# Connectors.net
KiCad netlist of a schematic drawn in Altium Designer
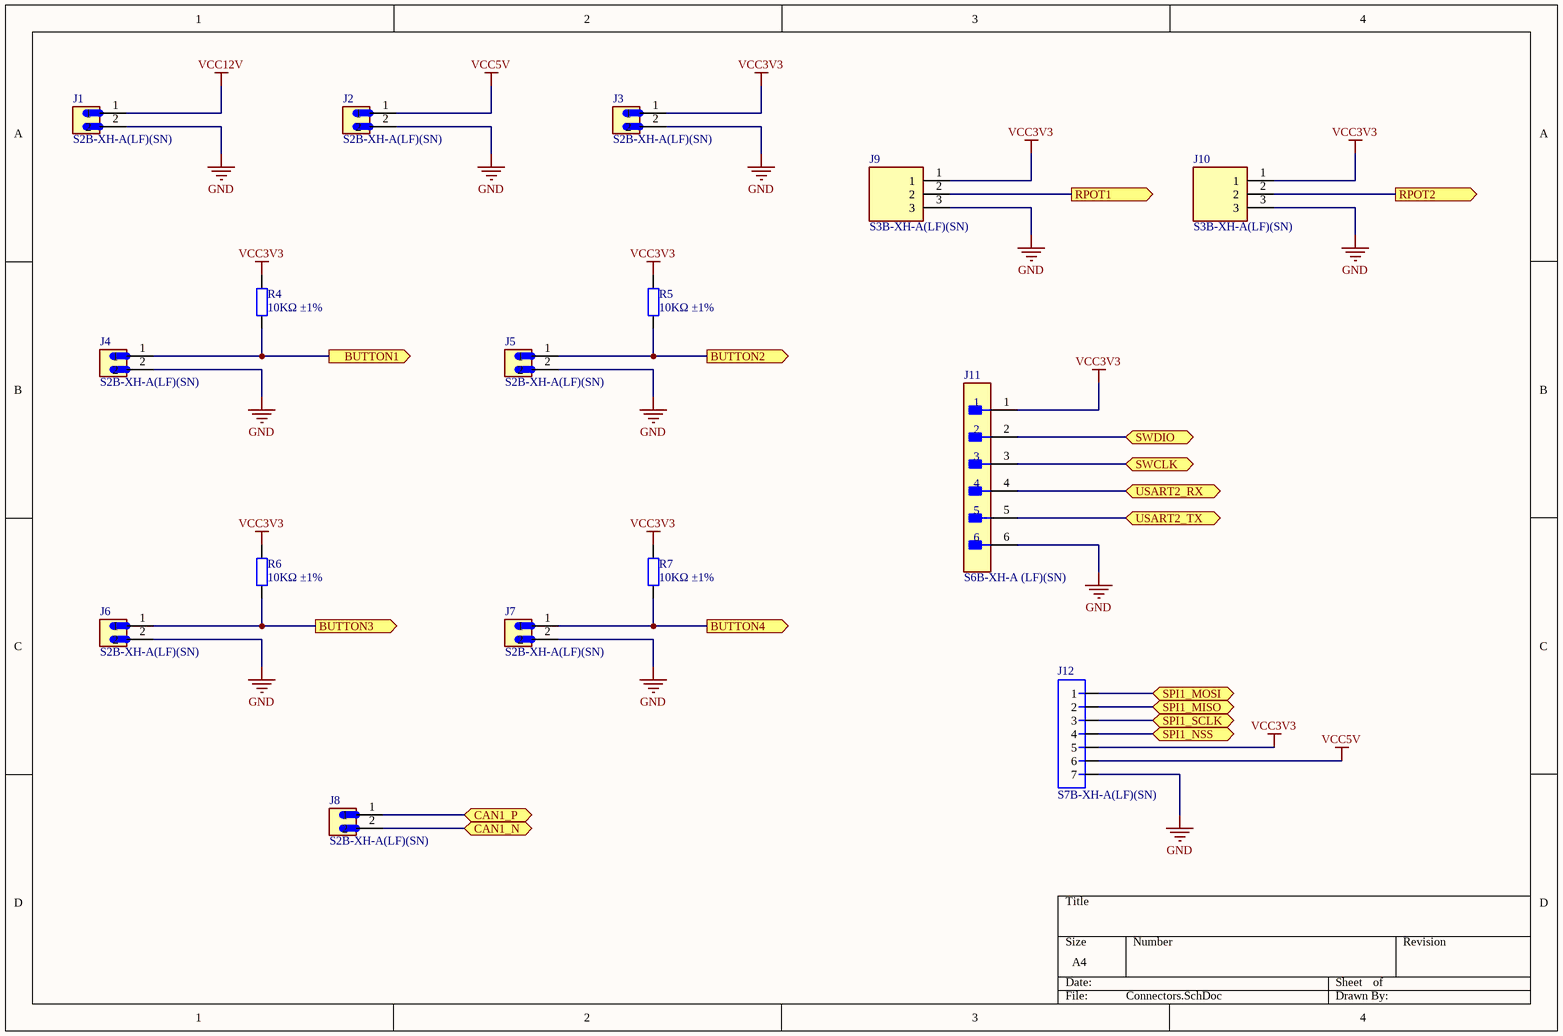
[diagram p0: Connectors.SchDoc]

(export (version "E")
  (design (tool "Eeschema 10.0.6"))
  (components
    (comp (ref "J1")
      (value "S2B-XH-A(LF)(SN)")
      (footprint "JST_S2B-XH-A(LF)(SN)")
      (description "Connector Header Through Hole, Right Angle 2 position 0.098 (2.50mm)")
      (fields (field (name "MF") "JST Sales") (field (name "DIGI-KEY_PART_NUMBER") "455-2257-ND"))
      (libsource (lib "S2B-XH-A_LF__SN_") (part "S2B-XH-A(LF)(SN)"))
    )
    (comp (ref "J2")
      (value "S2B-XH-A(LF)(SN)")
      (footprint "JST_S2B-XH-A(LF)(SN)")
      (description "Connector Header Through Hole, Right Angle 2 position 0.098 (2.50mm)")
      (fields (field (name "MF") "JST Sales") (field (name "DIGI-KEY_PART_NUMBER") "455-2257-ND"))
      (libsource (lib "S2B-XH-A_LF__SN_") (part "S2B-XH-A(LF)(SN)"))
    )
    (comp (ref "J3")
      (value "S2B-XH-A(LF)(SN)")
      (footprint "JST_S2B-XH-A(LF)(SN)")
      (description "Connector Header Through Hole, Right Angle 2 position 0.098 (2.50mm)")
      (fields (field (name "MF") "JST Sales") (field (name "DIGI-KEY_PART_NUMBER") "455-2257-ND"))
      (libsource (lib "S2B-XH-A_LF__SN_") (part "S2B-XH-A(LF)(SN)"))
    )
    (comp (ref "J4")
      (value "S2B-XH-A(LF)(SN)")
      (footprint "JST_S2B-XH-A(LF)(SN)")
      (description "Connector Header Through Hole, Right Angle 2 position 0.098 (2.50mm)")
      (fields (field (name "MF") "JST Sales") (field (name "DIGI-KEY_PART_NUMBER") "455-2257-ND"))
      (libsource (lib "S2B-XH-A_LF__SN_") (part "S2B-XH-A(LF)(SN)"))
    )
    (comp (ref "J5")
      (value "S2B-XH-A(LF)(SN)")
      (footprint "JST_S2B-XH-A(LF)(SN)")
      (description "Connector Header Through Hole, Right Angle 2 position 0.098 (2.50mm)")
      (fields (field (name "MF") "JST Sales") (field (name "DIGI-KEY_PART_NUMBER") "455-2257-ND"))
      (libsource (lib "S2B-XH-A_LF__SN_") (part "S2B-XH-A(LF)(SN)"))
    )
    (comp (ref "J6")
      (value "S2B-XH-A(LF)(SN)")
      (footprint "JST_S2B-XH-A(LF)(SN)")
      (description "Connector Header Through Hole, Right Angle 2 position 0.098 (2.50mm)")
      (fields (field (name "MF") "JST Sales") (field (name "DIGI-KEY_PART_NUMBER") "455-2257-ND"))
      (libsource (lib "S2B-XH-A_LF__SN_") (part "S2B-XH-A(LF)(SN)"))
    )
    (comp (ref "J7")
      (value "S2B-XH-A(LF)(SN)")
      (footprint "JST_S2B-XH-A(LF)(SN)")
      (description "Connector Header Through Hole, Right Angle 2 position 0.098 (2.50mm)")
      (fields (field (name "MF") "JST Sales") (field (name "DIGI-KEY_PART_NUMBER") "455-2257-ND"))
      (libsource (lib "S2B-XH-A_LF__SN_") (part "S2B-XH-A(LF)(SN)"))
    )
    (comp (ref "J8")
      (value "S2B-XH-A(LF)(SN)")
      (footprint "JST_S2B-XH-A(LF)(SN)")
      (description "Connector Header Through Hole, Right Angle 2 position 0.098 (2.50mm)")
      (fields (field (name "MF") "JST Sales") (field (name "DIGI-KEY_PART_NUMBER") "455-2257-ND"))
      (libsource (lib "S2B-XH-A_LF__SN_") (part "S2B-XH-A(LF)(SN)"))
    )
    (comp (ref "J9")
      (value "S3B-XH-A(LF)(SN)")
      (footprint "JST_S3B-XH-A(LF)(SN)")
      (fields (field (name "MF") "JST") (field (name "MP") "S3B-XH-A (LF)(SN)"))
      (libsource (lib "S3B-XH-A_LF__SN_") (part "S3B-XH-A(LF)(SN)"))
    )
    (comp (ref "J10")
      (value "S3B-XH-A(LF)(SN)")
      (footprint "JST_S3B-XH-A(LF)(SN)")
      (fields (field (name "MF") "JST") (field (name "MP") "S3B-XH-A (LF)(SN)"))
      (libsource (lib "S3B-XH-A_LF__SN_") (part "S3B-XH-A(LF)(SN)"))
    )
    (comp (ref "J11")
      (value "S6B-XH-A (LF)(SN)")
      (footprint "FP-S6B-XH-A_LF_SN-MFG")
      (description "CONN HEADER R/A 6POS 2.5MM")
      (libsource (lib "Altium Content Vault") (part "f2cb566baf1c37ab5a3b8e90bbeafd6"))
    )
    (comp (ref "J12")
      (value "S7B-XH-A(LF)(SN)")
      (footprint "JST_S7B-XH-A(LF)(SN)")
      (description "Connector Header Through Hole, Right Angle 7 position 0.098 _2.50mm_")
      (fields (field (name "MP") "S7B-XH-A_LF__SN_") (field (name "MF") "JST Sales"))
      (libsource (lib "S7B-XH-A_LF__SN_") (part "S7B-XH-A(LF)(SN)"))
    )
    (comp (ref "R4")
      (value "10KΩ ±1%")
      (footprint "0402_R")
      (description "Chip resistor")
      (fields (field (name "MANUFACTURER") "Uniroyal Elec") (field (name "PARTNUMBER") "0402WGF1002TCE"))
      (libsource (lib "RES") (part "0402 10K (1002) 1%"))
    )
    (comp (ref "R5")
      (value "10KΩ ±1%")
      (footprint "0402_R")
      (description "Chip resistor")
      (fields (field (name "MANUFACTURER") "Uniroyal Elec") (field (name "PARTNUMBER") "0402WGF1002TCE"))
      (libsource (lib "RES") (part "0402 10K (1002) 1%"))
    )
    (comp (ref "R6")
      (value "10KΩ ±1%")
      (footprint "0402_R")
      (description "Chip resistor")
      (fields (field (name "MANUFACTURER") "Uniroyal Elec") (field (name "PARTNUMBER") "0402WGF1002TCE"))
      (libsource (lib "RES") (part "0402 10K (1002) 1%"))
    )
    (comp (ref "R7")
      (value "10KΩ ±1%")
      (footprint "0402_R")
      (description "Chip resistor")
      (fields (field (name "MANUFACTURER") "Uniroyal Elec") (field (name "PARTNUMBER") "0402WGF1002TCE"))
      (libsource (lib "RES") (part "0402 10K (1002) 1%"))
    )
  )
  (nets
    (net (code "1") (name "/BUTTON1") (class "Default")
      (node (ref "J4") (pin "1") (pinfunction "1_1") (pintype "passive"))
      (node (ref "R4") (pin "1") (pinfunction "1_1") (pintype "passive"))
    )
    (net (code "2") (name "/BUTTON2") (class "Default")
      (node (ref "J5") (pin "1") (pinfunction "1_1") (pintype "passive"))
      (node (ref "R5") (pin "1") (pinfunction "1_1") (pintype "passive"))
    )
    (net (code "3") (name "/BUTTON3") (class "Default")
      (node (ref "J6") (pin "1") (pinfunction "1_1") (pintype "passive"))
      (node (ref "R6") (pin "1") (pinfunction "1_1") (pintype "passive"))
    )
    (net (code "4") (name "/BUTTON4") (class "Default")
      (node (ref "J7") (pin "1") (pinfunction "1_1") (pintype "passive"))
      (node (ref "R7") (pin "1") (pinfunction "1_1") (pintype "passive"))
    )
    (net (code "5") (name "/CAN1_N") (class "Default")
      (node (ref "J8") (pin "2") (pinfunction "2_2") (pintype "passive"))
    )
    (net (code "6") (name "/CAN1_P") (class "Default")
      (node (ref "J8") (pin "1") (pinfunction "1_1") (pintype "passive"))
    )
    (net (code "7") (name "/RPOT1") (class "Default")
      (node (ref "J9") (pin "2") (pinfunction "2_2") (pintype "passive"))
    )
    (net (code "8") (name "/RPOT2") (class "Default")
      (node (ref "J10") (pin "2") (pinfunction "2_2") (pintype "passive"))
    )
    (net (code "9") (name "/SPI1_MISO") (class "Default")
      (node (ref "J12") (pin "2") (pinfunction "2_2") (pintype "passive"))
    )
    (net (code "10") (name "/SPI1_MOSI") (class "Default")
      (node (ref "J12") (pin "1") (pinfunction "1_1") (pintype "passive"))
    )
    (net (code "11") (name "/SPI1_NSS") (class "Default")
      (node (ref "J12") (pin "4") (pinfunction "4_4") (pintype "passive"))
    )
    (net (code "12") (name "/SPI1_SCLK") (class "Default")
      (node (ref "J12") (pin "3") (pinfunction "3_3") (pintype "passive"))
    )
    (net (code "13") (name "/SWCLK") (class "Default")
      (node (ref "J11") (pin "3") (pinfunction "3_3") (pintype "passive"))
    )
    (net (code "14") (name "/SWDIO") (class "Default")
      (node (ref "J11") (pin "2") (pinfunction "2_2") (pintype "passive"))
    )
    (net (code "15") (name "/USART2_RX") (class "Default")
      (node (ref "J11") (pin "4") (pinfunction "4_4") (pintype "passive"))
    )
    (net (code "16") (name "/USART2_TX") (class "Default")
      (node (ref "J11") (pin "5") (pinfunction "5_5") (pintype "passive"))
    )
    (net (code "17") (name "GND") (class "Default")
      (node (ref "J1") (pin "2") (pinfunction "2_2") (pintype "passive"))
      (node (ref "J10") (pin "3") (pinfunction "3_3") (pintype "passive"))
      (node (ref "J11") (pin "6") (pinfunction "6_6") (pintype "passive"))
      (node (ref "J12") (pin "7") (pinfunction "7_7") (pintype "passive"))
      (node (ref "J2") (pin "2") (pinfunction "2_2") (pintype "passive"))
      (node (ref "J3") (pin "2") (pinfunction "2_2") (pintype "passive"))
      (node (ref "J4") (pin "2") (pinfunction "2_2") (pintype "passive"))
      (node (ref "J5") (pin "2") (pinfunction "2_2") (pintype "passive"))
      (node (ref "J6") (pin "2") (pinfunction "2_2") (pintype "passive"))
      (node (ref "J7") (pin "2") (pinfunction "2_2") (pintype "passive"))
      (node (ref "J9") (pin "3") (pinfunction "3_3") (pintype "passive"))
    )
    (net (code "18") (name "VCC3V3") (class "Default")
      (node (ref "J10") (pin "1") (pinfunction "1_1") (pintype "passive"))
      (node (ref "J11") (pin "1") (pinfunction "1_1") (pintype "passive"))
      (node (ref "J12") (pin "5") (pinfunction "5_5") (pintype "passive"))
      (node (ref "J3") (pin "1") (pinfunction "1_1") (pintype "passive"))
      (node (ref "J9") (pin "1") (pinfunction "1_1") (pintype "passive"))
      (node (ref "R4") (pin "2") (pinfunction "2_2") (pintype "passive"))
      (node (ref "R5") (pin "2") (pinfunction "2_2") (pintype "passive"))
      (node (ref "R6") (pin "2") (pinfunction "2_2") (pintype "passive"))
      (node (ref "R7") (pin "2") (pinfunction "2_2") (pintype "passive"))
    )
    (net (code "19") (name "VCC5V") (class "Default")
      (node (ref "J12") (pin "6") (pinfunction "6_6") (pintype "passive"))
      (node (ref "J2") (pin "1") (pinfunction "1_1") (pintype "passive"))
    )
    (net (code "20") (name "VCC12V") (class "Default")
      (node (ref "J1") (pin "1") (pinfunction "1_1") (pintype "passive"))
    )
  )
)
